# Sheet1.net
KiCad netlist of a schematic drawn in Altium Designer
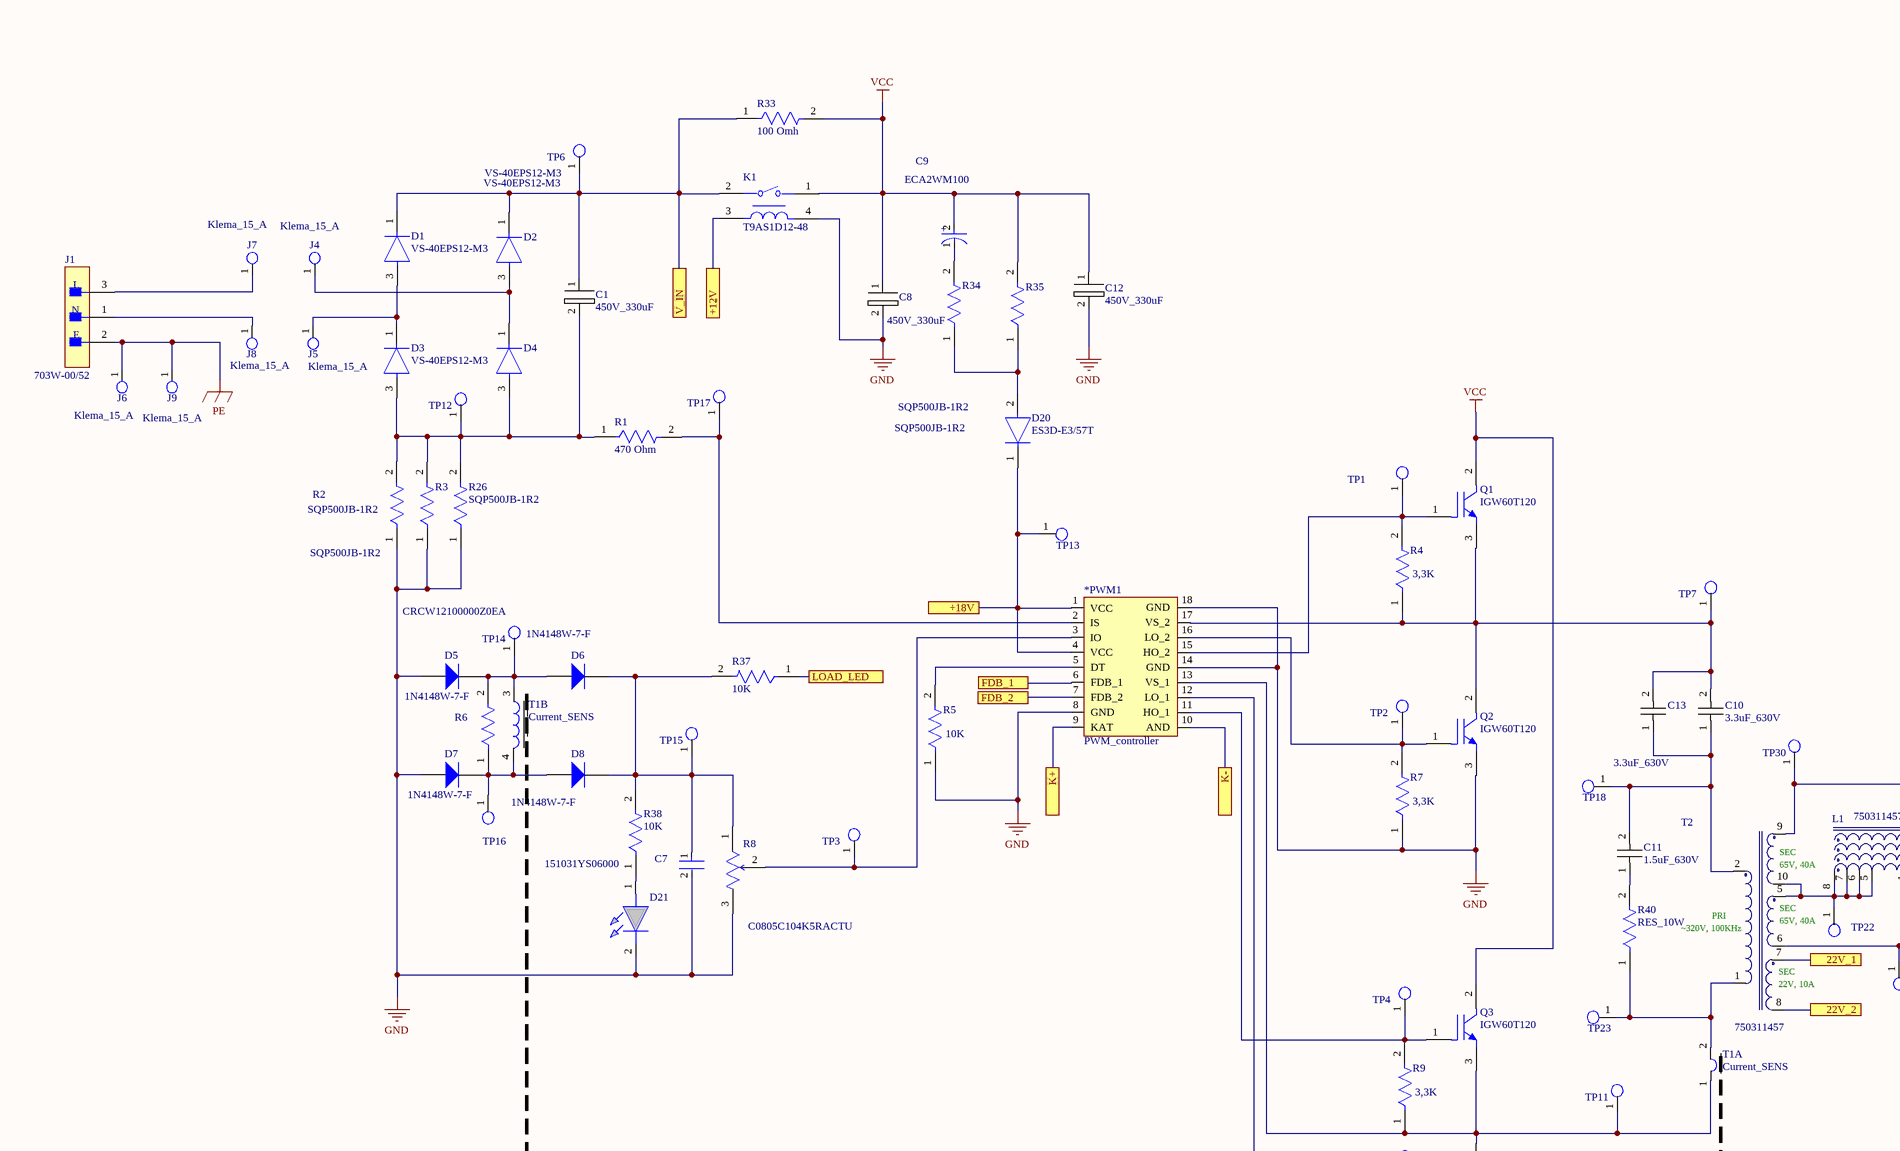
[diagram p0: Sheet1.SchDoc, top left]
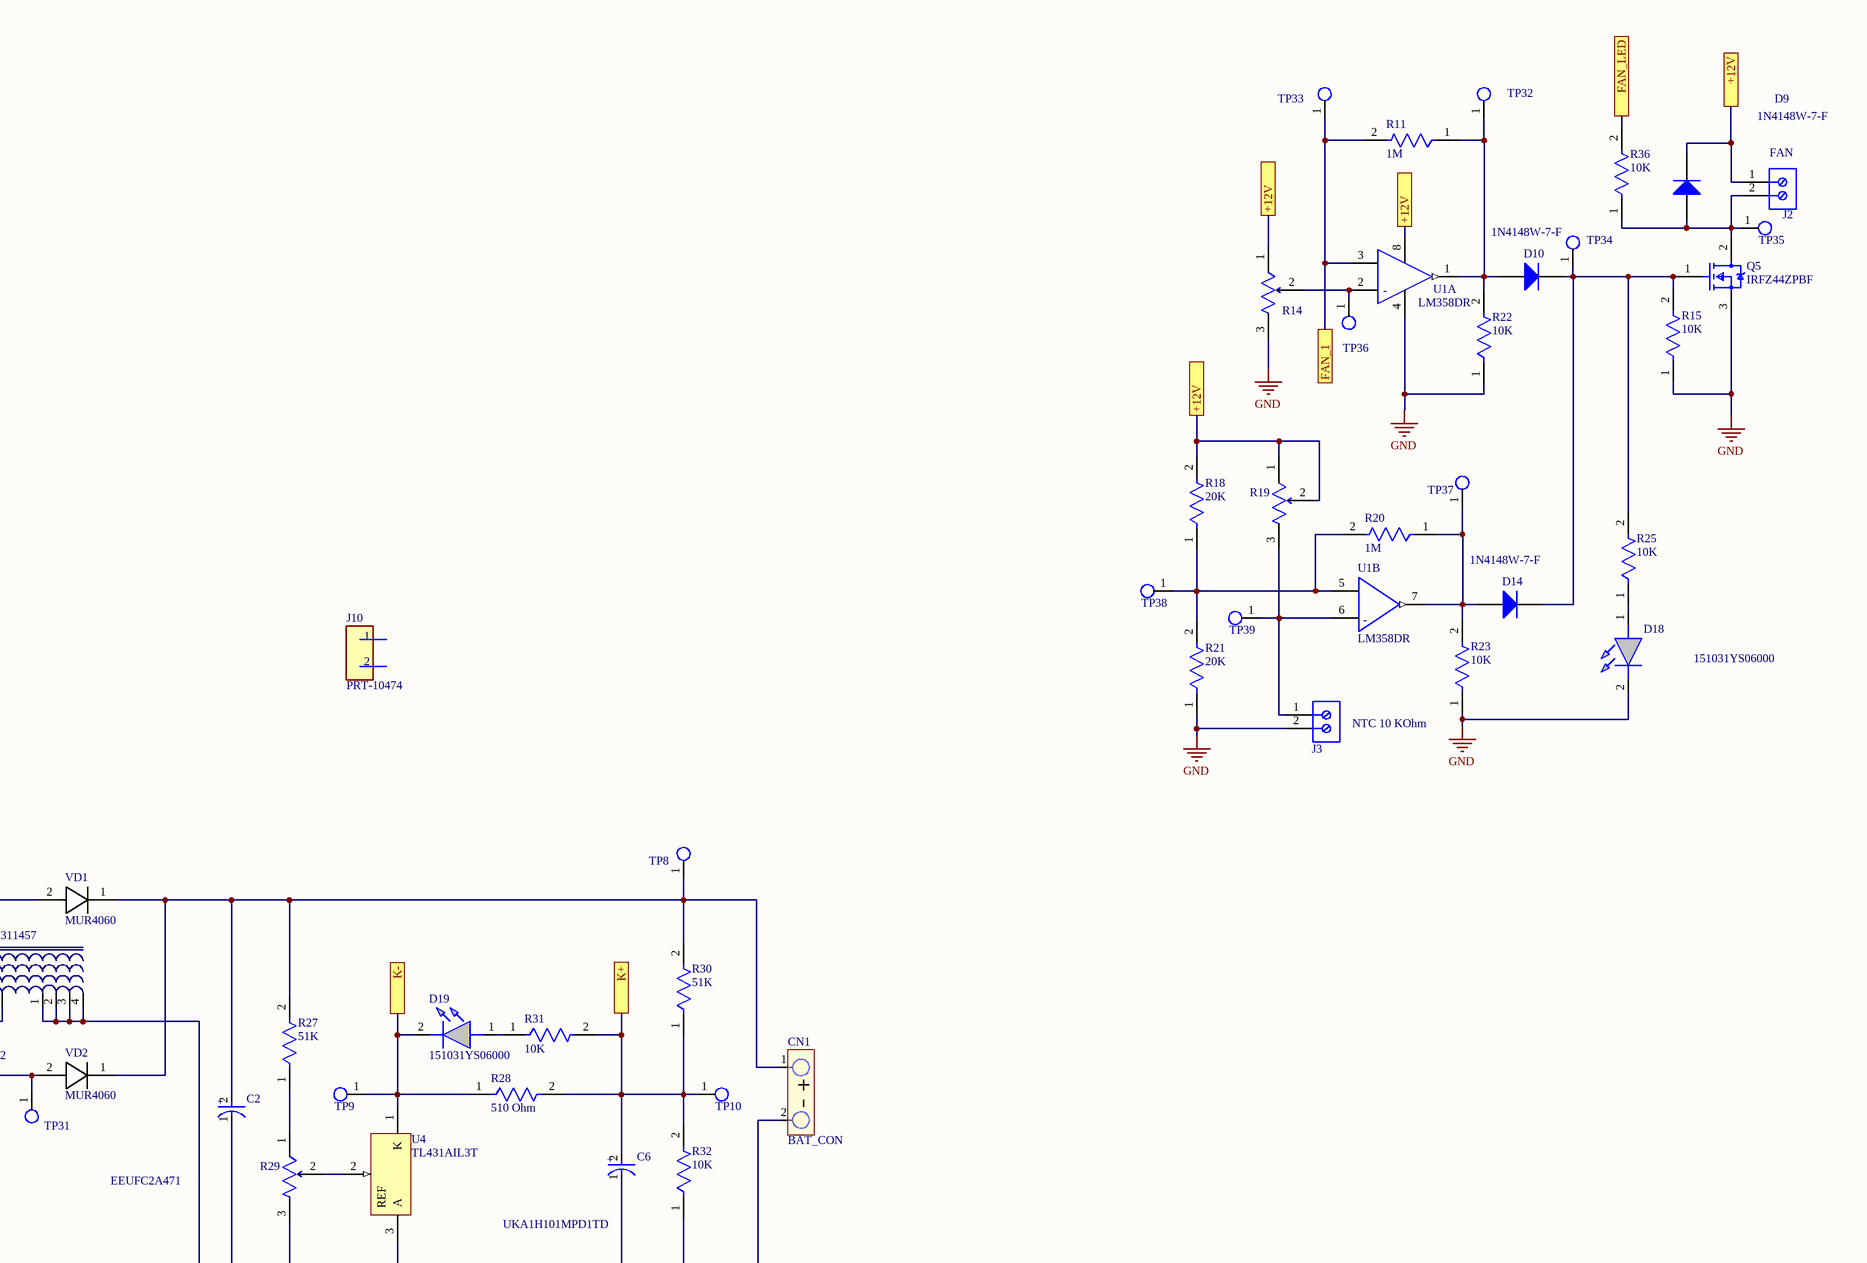
[diagram p1: Sheet1.SchDoc, top right]
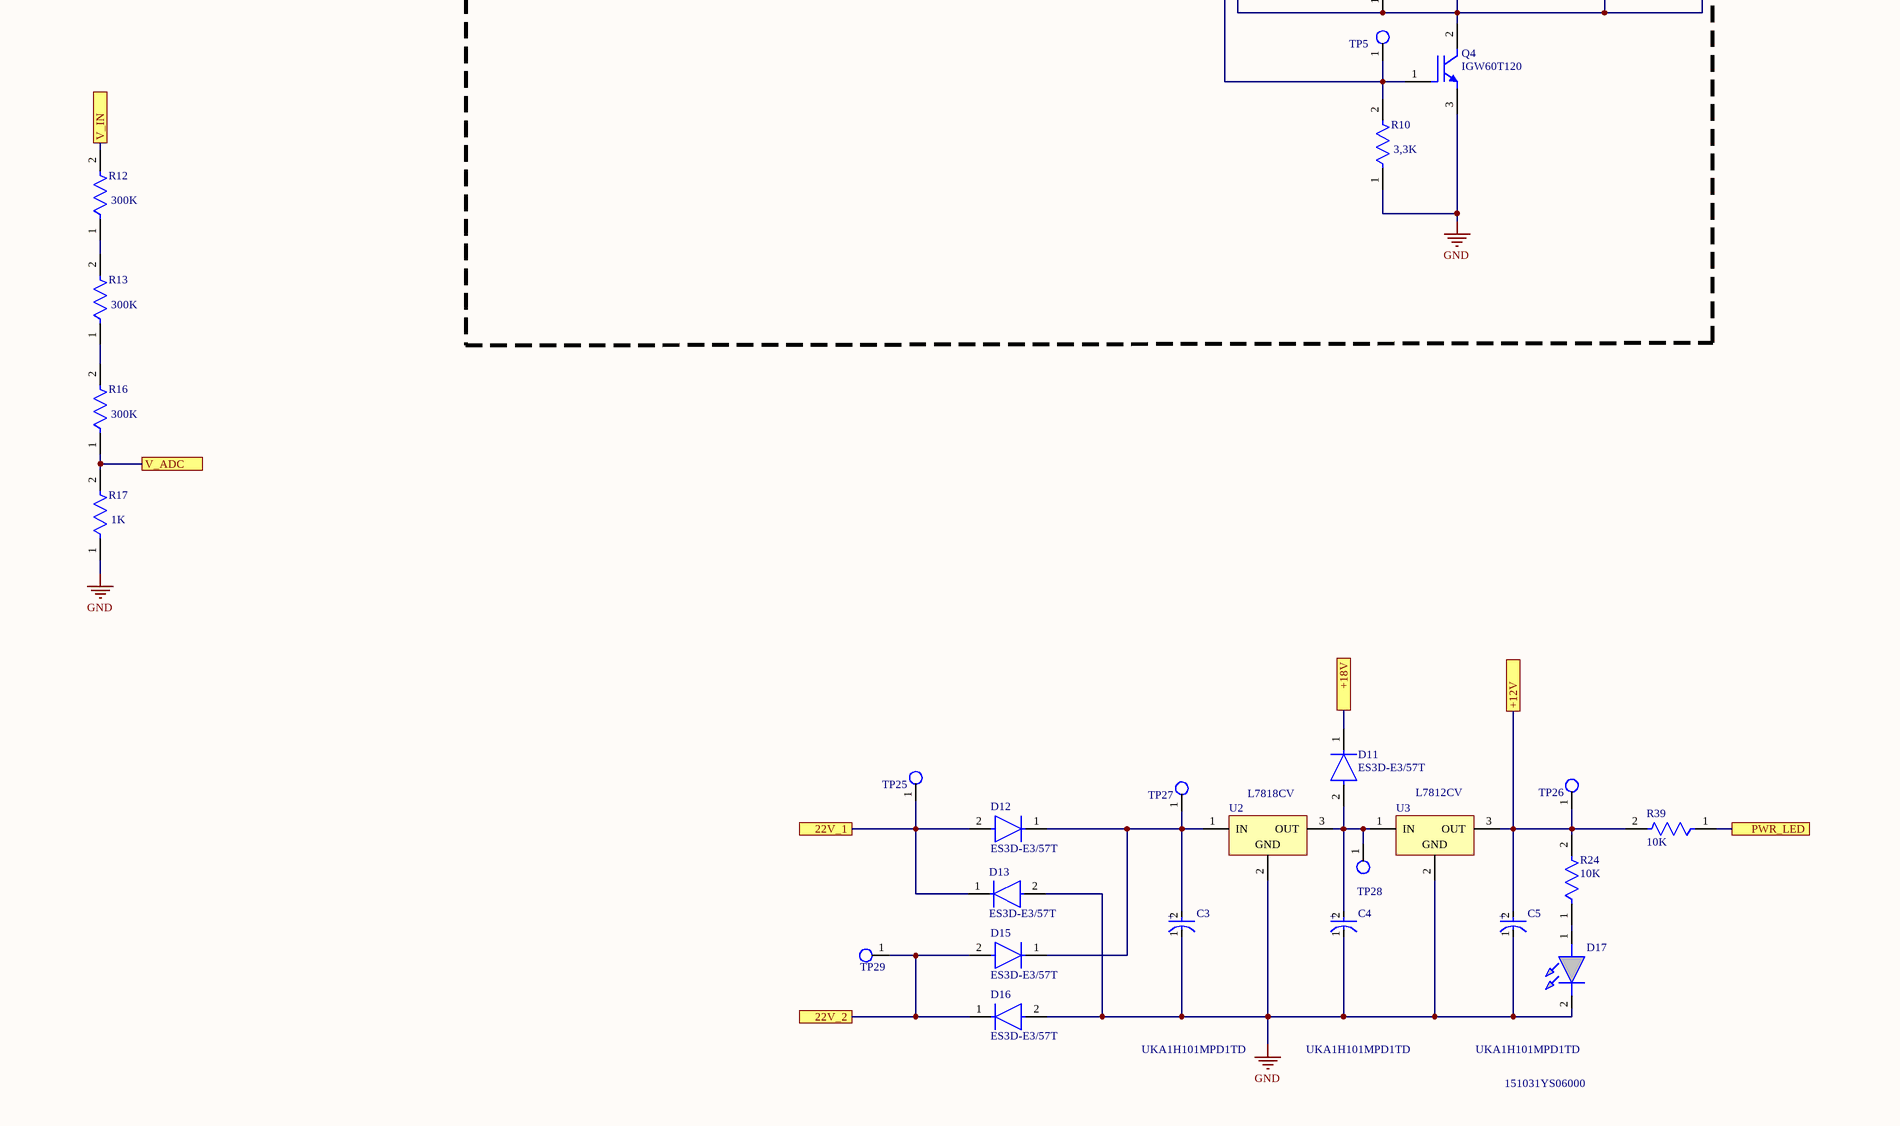
[diagram p2: Sheet1.SchDoc, bottom left]
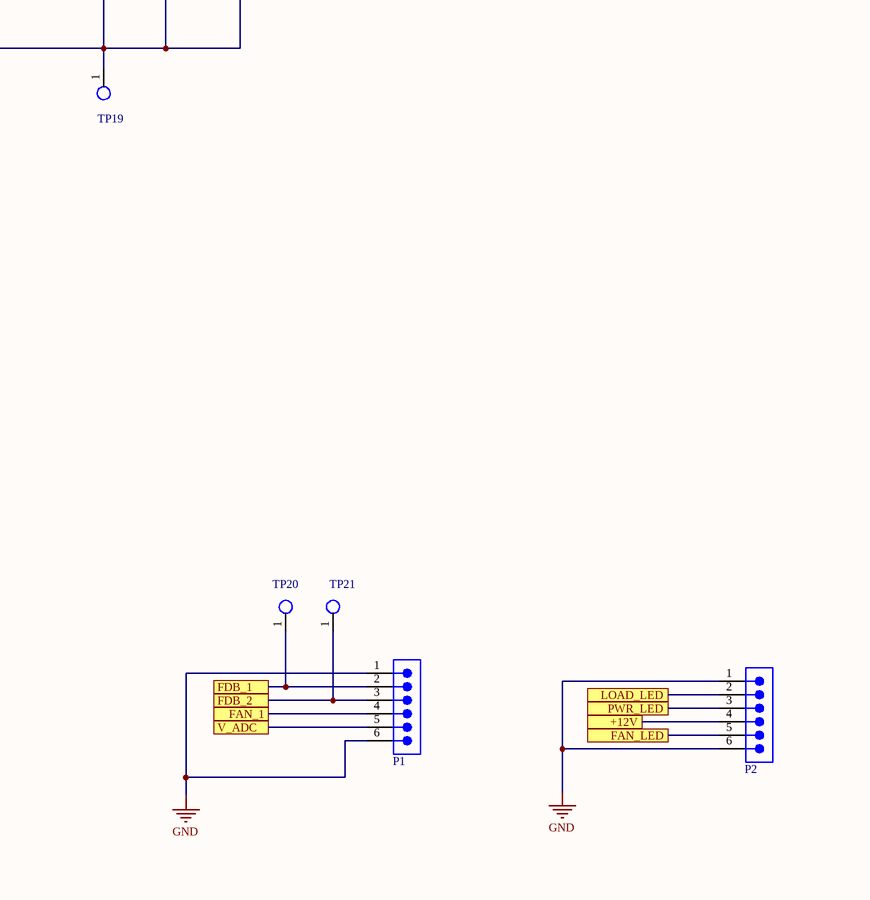
[diagram p3: Sheet1.SchDoc, bottom right]

(export (version "E")
  (design (tool "Eeschema 10.0.6"))
  (components
    (comp (ref "*PWM1")
      (value "PWM_controller")
      (footprint "PWM_controller")
      (libsource (lib "PWM_controller") (part "PWM_controller"))
    )
    (comp (ref "C1")
      (value "450V_330uF")
      (footprint "CAP_450V_330uF")
      (libsource (lib "CAP_450V_330uF") (part "CAP_450V_330uF"))
    )
    (comp (ref "C2")
      (value "EEUFC2A471")
      (footprint "FP-RAD-TH-D_16_0_5-L_40_2-MFG")
      (description "Aluminum Electrolytic Capacitors (Radial Lead Type) AEC-Q200 Qualified 470uF ±20% 100V")
      (fields (field (name "VOLTAGE") "100V") (field (name "TOLERANCE") "20%"))
      (libsource (lib "Altium Content Vault") (part "203bc49f2ac43e59fd269a8c329ed05"))
    )
    (comp (ref "C3")
      (value "UKA1H101MPD1TD")
      (footprint "FP-UKA1H101MPD1TD-MFG")
      (description "CAP ALUM 100UF 20% 50V RADIAL")
      (fields (field (name "TOLERANCE") "20%"))
      (libsource (lib "Altium Content Vault") (part "203bc49f2ac43e59fd269a8c329ed05"))
    )
    (comp (ref "C4")
      (value "UKA1H101MPD1TD")
      (footprint "FP-UKA1H101MPD1TD-MFG")
      (description "CAP ALUM 100UF 20% 50V RADIAL")
      (fields (field (name "TOLERANCE") "20%"))
      (libsource (lib "Altium Content Vault") (part "203bc49f2ac43e59fd269a8c329ed05"))
    )
    (comp (ref "C5")
      (value "UKA1H101MPD1TD")
      (footprint "FP-UKA1H101MPD1TD-MFG")
      (description "CAP ALUM 100UF 20% 50V RADIAL")
      (fields (field (name "TOLERANCE") "20%"))
      (libsource (lib "Altium Content Vault") (part "203bc49f2ac43e59fd269a8c329ed05"))
    )
    (comp (ref "C6")
      (value "UKA1H101MPD1TD")
      (footprint "FP-UKA1H101MPD1TD-MFG")
      (description "CAP ALUM 100UF 20% 50V RADIAL")
      (fields (field (name "TOLERANCE") "20%"))
      (libsource (lib "Altium Content Vault") (part "203bc49f2ac43e59fd269a8c329ed05"))
    )
    (comp (ref "C7")
      (value "C0805C104K5RACTU")
      (footprint "FP-C0805C-DN-MFG")
      (description "CAP CER 0.1UF 50V X7R 0805")
      (fields
        (field (name "MANUFACTURER") "KEMET")
        (field (name "OCTOPART") "https://octopart.com/c0805c104k5ractu-kemet-143926")
      )
      (libsource (lib "Altium Content Vault") (part "b4654b650e69147ec39a6b967a45e02"))
    )
    (comp (ref "C8")
      (value "450V_330uF")
      (footprint "CAP_450V_470uF")
      (libsource (lib "CAP_450V_330uF") (part "CAP_450V_330uF"))
    )
    (comp (ref "C9")
      (value "ECA2WM100")
      (footprint "FP-RAD-TH-D_12_5_0_5-L_20-MFG")
      (description "Aluminum Electrolytic Capacitors (Radial Lead Type) 10uF ±20% 450V")
      (fields (field (name "TOLERANCE") "20%") (field (name "VOLTAGE") "450V"))
      (libsource (lib "Altium Content Vault") (part "a00bbbee19879c290e62620ae7e47b1"))
    )
    (comp (ref "C10")
      (value "3.3uF_630V")
      (footprint "CAP_4.7uF_630V")
      (libsource (lib "CAP_3.3uF_630V") (part "3.3uF_630V"))
    )
    (comp (ref "C11")
      (value "1.5uF_630V")
      (footprint "CAP_1.5uf_400V")
      (libsource (lib "CAP_3.3uF_630V") (part "3.3uF_630V"))
    )
    (comp (ref "C12")
      (value "450V_330uF")
      (footprint "CAP_450V_470uF")
      (libsource (lib "CAP_450V_330uF") (part "CAP_450V_330uF"))
    )
    (comp (ref "C13")
      (value "3.3uF_630V")
      (footprint "CAP_4.7uF_630V")
      (libsource (lib "CAP_3.3uF_630V") (part "3.3uF_630V"))
    )
    (comp (ref "CN1")
      (value "BAT_CON")
      (footprint "Batarey_connector")
      (description "Batarey_connection")
      (libsource (lib "Batarey_connector") (part "BAT_CON"))
    )
    (comp (ref "D1")
      (value "VS-40EPS12-M3")
      (footprint "FP-96144-MFG")
      (description "DIODE GP 1.2KV 40A TO247AC")
      (libsource (lib "Altium Content Vault") (part "ac9d09a08f7f4319d7c77abc64a3d8a"))
    )
    (comp (ref "D2")
      (value "VS-40EPS12-M3")
      (footprint "FP-96144-MFG")
      (description "DIODE GP 1.2KV 40A TO247AC")
      (libsource (lib "Altium Content Vault") (part "ac9d09a08f7f4319d7c77abc64a3d8a"))
    )
    (comp (ref "D3")
      (value "VS-40EPS12-M3")
      (footprint "FP-96144-MFG")
      (description "DIODE GP 1.2KV 40A TO247AC")
      (libsource (lib "Altium Content Vault") (part "ac9d09a08f7f4319d7c77abc64a3d8a"))
    )
    (comp (ref "D4")
      (value "VS-40EPS12-M3")
      (footprint "FP-96144-MFG")
      (description "DIODE GP 1.2KV 40A TO247AC")
      (libsource (lib "Altium Content Vault") (part "ac9d09a08f7f4319d7c77abc64a3d8a"))
    )
    (comp (ref "D5")
      (value "1N4148W-7-F")
      (footprint "DIOD-SOD123-2_V")
      (description "Fast Switching Diode, 100 V, 0.15 A, -65 to 150 degC, 2-Pin?SOD123, RoHS, Tape and Reel")
      (fields (field (name "MANUFACTURER") "DiodesIncorporated"))
      (libsource (lib "Altium Content Vault") (part "D-AK-2"))
    )
    (comp (ref "D6")
      (value "1N4148W-7-F")
      (footprint "DIOD-SOD123-2_V")
      (description "Fast Switching Diode, 100 V, 0.15 A, -65 to 150 degC, 2-Pin?SOD123, RoHS, Tape and Reel")
      (fields (field (name "MANUFACTURER") "DiodesIncorporated"))
      (libsource (lib "Altium Content Vault") (part "D-AK-2"))
    )
    (comp (ref "D7")
      (value "1N4148W-7-F")
      (footprint "DIOD-SOD123-2_V")
      (description "Fast Switching Diode, 100 V, 0.15 A, -65 to 150 degC, 2-Pin?SOD123, RoHS, Tape and Reel")
      (fields (field (name "MANUFACTURER") "DiodesIncorporated"))
      (libsource (lib "Altium Content Vault") (part "D-AK-2"))
    )
    (comp (ref "D8")
      (value "1N4148W-7-F")
      (footprint "DIOD-SOD123-2_V")
      (description "Fast Switching Diode, 100 V, 0.15 A, -65 to 150 degC, 2-Pin?SOD123, RoHS, Tape and Reel")
      (fields (field (name "MANUFACTURER") "DiodesIncorporated"))
      (libsource (lib "Altium Content Vault") (part "D-AK-2"))
    )
    (comp (ref "D9")
      (value "1N4148W-7-F")
      (footprint "DIOD-SOD123-2_V")
      (description "Fast Switching Diode, 100 V, 0.15 A, -65 to 150 degC, 2-Pin?SOD123, RoHS, Tape and Reel")
      (fields (field (name "MANUFACTURER") "DiodesIncorporated"))
      (libsource (lib "Altium Content Vault") (part "D-AK-2"))
    )
    (comp (ref "D10")
      (value "1N4148W-7-F")
      (footprint "DIOD-SOD123-2_V")
      (description "Fast Switching Diode, 100 V, 0.15 A, -65 to 150 degC, 2-Pin?SOD123, RoHS, Tape and Reel")
      (fields (field (name "MANUFACTURER") "DiodesIncorporated"))
      (libsource (lib "Altium Content Vault") (part "D-AK-2"))
    )
    (comp (ref "D11")
      (value "ES3D-E3/57T")
      (footprint "FP-95402-MFG")
      (description "DIODE GEN PURP 200V 3A DO214AB")
      (fields
        (field (name "OCTOPART") "https://octopart.com/es3d-e3%2F57t-vishay-39550290")
        (field (name "MANUFACTURER") "Vishay")
      )
      (libsource (lib "Altium Content Vault") (part "d7152d700b627762746794eb795d46e"))
    )
    (comp (ref "D12")
      (value "ES3D-E3/57T")
      (footprint "FP-95402-MFG")
      (description "DIODE GEN PURP 200V 3A DO214AB")
      (fields
        (field (name "OCTOPART") "https://octopart.com/es3d-e3%2F57t-vishay-39550290")
        (field (name "MANUFACTURER") "Vishay")
      )
      (libsource (lib "Altium Content Vault") (part "d7152d700b627762746794eb795d46e"))
    )
    (comp (ref "D13")
      (value "ES3D-E3/57T")
      (footprint "FP-95402-MFG")
      (description "DIODE GEN PURP 200V 3A DO214AB")
      (fields
        (field (name "OCTOPART") "https://octopart.com/es3d-e3%2F57t-vishay-39550290")
        (field (name "MANUFACTURER") "Vishay")
      )
      (libsource (lib "Altium Content Vault") (part "d7152d700b627762746794eb795d46e"))
    )
    (comp (ref "D14")
      (value "1N4148W-7-F")
      (footprint "DIOD-SOD123-2_V")
      (description "Fast Switching Diode, 100 V, 0.15 A, -65 to 150 degC, 2-Pin?SOD123, RoHS, Tape and Reel")
      (fields (field (name "MANUFACTURER") "DiodesIncorporated"))
      (libsource (lib "Altium Content Vault") (part "D-AK-2"))
    )
    (comp (ref "D15")
      (value "ES3D-E3/57T")
      (footprint "FP-95402-MFG")
      (description "DIODE GEN PURP 200V 3A DO214AB")
      (fields
        (field (name "OCTOPART") "https://octopart.com/es3d-e3%2F57t-vishay-39550290")
        (field (name "MANUFACTURER") "Vishay")
      )
      (libsource (lib "Altium Content Vault") (part "d7152d700b627762746794eb795d46e"))
    )
    (comp (ref "D16")
      (value "ES3D-E3/57T")
      (footprint "FP-95402-MFG")
      (description "DIODE GEN PURP 200V 3A DO214AB")
      (fields
        (field (name "OCTOPART") "https://octopart.com/es3d-e3%2F57t-vishay-39550290")
        (field (name "MANUFACTURER") "Vishay")
      )
      (libsource (lib "Altium Content Vault") (part "d7152d700b627762746794eb795d46e"))
    )
    (comp (ref "D17")
      (value "151031YS06000")
      (footprint "LED_BLUE")
      (description "WURTH ELEKTRONIK - 151031YS06000 - LED, Yellow, Through Hole, T-1 (3mm), 30 mA, 2 V, 590 nm")
      (fields (field (name "MOUSER PART NUMBER") "710-151031YS06000"))
      (libsource (lib "Optic-LED") (part "151031YS06000"))
    )
    (comp (ref "D18")
      (value "151031YS06000")
      (footprint "Wurth_Electronics_0_MFG")
      (description "WURTH ELEKTRONIK - 151031YS06000 - LED, Yellow, Through Hole, T-1 (3mm), 30 mA, 2 V, 590 nm")
      (fields (field (name "MOUSER PART NUMBER") "710-151031YS06000"))
      (libsource (lib "Optic-LED") (part "151031YS06000"))
    )
    (comp (ref "D19")
      (value "151031YS06000")
      (footprint "LED_Yellow")
      (description "WURTH ELEKTRONIK - 151031YS06000 - LED, Yellow, Through Hole, T-1 (3mm), 30 mA, 2 V, 590 nm")
      (fields (field (name "MOUSER PART NUMBER") "710-151031YS06000"))
      (libsource (lib "Optic-LED") (part "151031YS06000"))
    )
    (comp (ref "D20")
      (value "ES3D-E3/57T")
      (footprint "FP-95402-MFG")
      (description "DIODE GEN PURP 200V 3A DO214AB")
      (fields
        (field (name "OCTOPART") "https://octopart.com/es3d-e3%2F57t-vishay-39550290")
        (field (name "MANUFACTURER") "Vishay")
      )
      (libsource (lib "Altium Content Vault") (part "d7152d700b627762746794eb795d46e"))
    )
    (comp (ref "D21")
      (value "151031YS06000")
      (footprint "LED_GREEN")
      (description "WURTH ELEKTRONIK - 151031YS06000 - LED, Yellow, Through Hole, T-1 (3mm), 30 mA, 2 V, 590 nm")
      (fields (field (name "MOUSER PART NUMBER") "710-151031YS06000"))
      (libsource (lib "Optic-LED") (part "151031YS06000"))
    )
    (comp (ref "J1")
      (value "703W-00/52")
      (footprint "FP-703W-00-52-MFG")
      (description "PWR ENT RCPT IEC320-C14 PNL SLDR")
      (libsource (lib "Altium Content Vault") (part "d3fa5aafac2488dd744475722bda3d4"))
    )
    (comp (ref "J2")
      (value "691137710002")
      (footprint "691137710002")
      (description "WR-TBL Series 1377 Horizontal Entry, THT, pitch 5mm, 2p")
      (fields (field (name "MANUFACTURER") "Wurth Elektronik"))
      (libsource (lib "Altium_WR-TBL (rev23a)") (part "691137710002"))
    )
    (comp (ref "J3")
      (value "691137710002")
      (footprint "691137710002")
      (description "WR-TBL Series 1377 Horizontal Entry, THT, pitch 5mm, 2p")
      (fields (field (name "MANUFACTURER") "Wurth Elektronik"))
      (libsource (lib "Altium_WR-TBL (rev23a)") (part "691137710002"))
    )
    (comp (ref "J4")
      (value "Klema_15_A")
      (footprint "Klema_PCB_15A")
      (libsource (lib "Klema PCB_15_A") (part "Klema_15_A"))
    )
    (comp (ref "J5")
      (value "Klema_15_A")
      (footprint "Klema_PCB_15A")
      (libsource (lib "Klema PCB_15_A") (part "Klema_15_A"))
    )
    (comp (ref "J6")
      (value "Klema_15_A")
      (footprint "Klema_PCB_15A")
      (libsource (lib "Klema PCB_15_A") (part "Klema_15_A"))
    )
    (comp (ref "J7")
      (value "Klema_15_A")
      (footprint "Klema_PCB_15A")
      (libsource (lib "Klema PCB_15_A") (part "Klema_15_A"))
    )
    (comp (ref "J8")
      (value "Klema_15_A")
      (footprint "Klema_PCB_15A")
      (libsource (lib "Klema PCB_15_A") (part "Klema_15_A"))
    )
    (comp (ref "J9")
      (value "Klema_15_A")
      (footprint "Klema_PCB_15A")
      (libsource (lib "Klema PCB_15_A") (part "Klema_15_A"))
    )
    (comp (ref "J10")
      (value "PRT-10474")
      (footprint "FP-PRT-10474-MFG")
      (description "XT60 CONNECTORS MALE/FEMALE PAIR")
      (libsource (lib "Altium Content Vault") (part "e9d95e9eb6564353a08a501d7ea6c79"))
    )
    (comp (ref "K1")
      (value "T9AS1D12-48")
      (footprint "NT90RNCS12CB")
      (description "RELAY GEN PURPOSE SPST 30A 48V")
      (libsource (lib "RelayNT90RNCS12CB") (part "CMP-03396-000117-1"))
    )
    (comp (ref "L1")
      (value "750311457")
      (footprint "Transformer")
      (description "Drosel")
      (fields (field (name "MANUFACTURER") "Wuerth Elektronik"))
      (libsource (lib "DROSEL") (part "DROSEL"))
    )
    (comp (ref "P1")
      (value "61900611121")
      (footprint "61900611121")
      (description "WR-WTB THT Male Vertical Locking Header, pitch 2.54mm, 6pins")
      (fields (field (name "MANUFACTURER") "Wurth Elektronik"))
      (libsource (lib "Altium_WR-WTB (rev22b)") (part "61900611121"))
    )
    (comp (ref "P2")
      (value "61900611121")
      (footprint "61900611121")
      (description "WR-WTB THT Male Vertical Locking Header, pitch 2.54mm, 6pins")
      (fields (field (name "MANUFACTURER") "Wurth Elektronik"))
      (libsource (lib "Altium_WR-WTB (rev22b)") (part "61900611121"))
    )
    (comp (ref "Q1")
      (value "IGW60T120")
      (footprint "TO-264-3")
      (description "Low Loss IGBT in TrenchStop and Fieldstop Technology, PG-TO247-3-44, Tube, Green")
      (fields (field (name "MANUFACTURER") "Infineon"))
      (libsource (lib "IGBT 60N120") (part "CMP-1168-00042-1"))
    )
    (comp (ref "Q2")
      (value "IGW60T120")
      (footprint "TO-264-3")
      (description "Low Loss IGBT in TrenchStop and Fieldstop Technology, PG-TO247-3-44, Tube, Green")
      (fields (field (name "MANUFACTURER") "Infineon"))
      (libsource (lib "IGBT 60N120") (part "CMP-1168-00042-1"))
    )
    (comp (ref "Q3")
      (value "IGW60T120")
      (footprint "TO-264-3")
      (description "Low Loss IGBT in TrenchStop and Fieldstop Technology, PG-TO247-3-44, Tube, Green")
      (fields (field (name "MANUFACTURER") "Infineon"))
      (libsource (lib "IGBT 60N120") (part "CMP-1168-00042-1"))
    )
    (comp (ref "Q4")
      (value "IGW60T120")
      (footprint "TO-264-3")
      (description "Low Loss IGBT in TrenchStop and Fieldstop Technology, PG-TO247-3-44, Tube, Green")
      (fields (field (name "MANUFACTURER") "Infineon"))
      (libsource (lib "IGBT 60N120") (part "CMP-1168-00042-1"))
    )
    (comp (ref "Q5")
      (value "IRFZ44ZPBF")
      (footprint "FP-PG-TO220-3-MFG")
      (description "MOSFET N-CH 55V 51A TO220AB")
      (libsource (lib "Altium Content Vault") (part "b09f7f152735e370c1ea22a33fa83d6"))
    )
    (comp (ref "R1")
      (value "470 Ohm")
      (footprint "FP-CRCW0805-e3-MFG")
      (description "RES Thick Film, 470Ω, 1%, 0.125W, 100ppm/°C, 0805")
      (fields (field (name "TOLERANCE") "1%"))
      (libsource (lib "Pasive_components") (part "CMP-2001-04908-2"))
    )
    (comp (ref "R2")
      (value "SQP500JB-1R2")
      (footprint "FP-SQP500-MFG")
      (description "RES 1.2 OHM 5W 5% AXIAL")
      (fields
        (field (name "OCTOPART") "https://octopart.com/sqp500jb-1r2-yageo-1162571")
        (field (name "MANUFACTURER") "Yageo")
      )
      (libsource (lib "Pasive_components") (part "CMP-03413-000003-1"))
    )
    (comp (ref "R3")
      (value "SQP500JB-1R2")
      (footprint "FP-SQP500-MFG")
      (description "RES 1.2 OHM 5W 5% AXIAL")
      (fields
        (field (name "OCTOPART") "https://octopart.com/sqp500jb-1r2-yageo-1162571")
        (field (name "MANUFACTURER") "Yageo")
      )
      (libsource (lib "Pasive_components") (part "CMP-03413-000003-1"))
    )
    (comp (ref "R4")
      (value "3,3K")
      (footprint "FP-CRCW1210-e3-IPC_A")
      (description "RES SMD 3,3K OHM 1% 1/2W 1992")
      (libsource (lib "Pasive_components") (part "CMP-2005-01987-2"))
    )
    (comp (ref "R5")
      (value "10K")
      (footprint "FP-CRCW1210-e3-IPC_A")
      (description "RES SMD 10K OHM 1% 1/2W 1992")
      (libsource (lib "Pasive_components") (part "CMP-2005-01987-2"))
    )
    (comp (ref "R6")
      (value "CRCW12100000Z0EA")
      (footprint "FP-CRCW1210-e3-IPC_A")
      (description "RES SMD 205K OHM 1% 1/2W 1992")
      (libsource (lib "Pasive_components") (part "CMP-2005-01987-2"))
    )
    (comp (ref "R7")
      (value "3,3K")
      (footprint "FP-CRCW1210-e3-IPC_A")
      (description "RES SMD 3,3K OHM 1% 1/2W 1992")
      (libsource (lib "Pasive_components") (part "CMP-2005-01987-2"))
    )
    (comp (ref "R8")
      (value "3296W-1-202LF")
      (footprint "Bourns_3296W_MFG")
      (libsource (lib "Pasive_components") (part "3296W-1-202LF"))
    )
    (comp (ref "R9")
      (value "3,3K")
      (footprint "FP-CRCW1210-e3-IPC_A")
      (description "RES SMD 3,3K OHM 1% 1/2W 1992")
      (libsource (lib "Pasive_components") (part "CMP-2005-01987-2"))
    )
    (comp (ref "R10")
      (value "3,3K")
      (footprint "FP-CRCW1210-e3-IPC_A")
      (description "RES SMD 3,3K OHM 1% 1/2W 1992")
      (libsource (lib "Pasive_components") (part "CMP-2005-01987-2"))
    )
    (comp (ref "R11")
      (value "1M")
      (footprint "FP-CRCW0805-e3-MFG")
      (description "RES Thick Film, 1MΩ, 1%, 0.125W, 100ppm/°C, 0805")
      (fields (field (name "TOLERANCE") "1%"))
      (libsource (lib "Pasive_components") (part "CMP-2001-04908-2"))
    )
    (comp (ref "R12")
      (value "300K")
      (footprint "FP-CRCW1210-e3-IPC_A")
      (description "RES SMD 300K OHM 1% 1/2W 1992")
      (libsource (lib "Pasive_components") (part "CMP-2005-01987-2"))
    )
    (comp (ref "R13")
      (value "300K")
      (footprint "FP-CRCW1210-e3-IPC_A")
      (description "RES SMD 300K OHM 1% 1/2W 1992")
      (libsource (lib "Pasive_components") (part "CMP-2005-01987-2"))
    )
    (comp (ref "R14")
      (value "3296W-1-202LF")
      (footprint "Bourns_3296W_MFG")
      (libsource (lib "Pasive_components") (part "3296W-1-202LF"))
    )
    (comp (ref "R15")
      (value "10K")
      (footprint "FP-CRCW0805-e3-MFG")
      (description "RES Thick Film, 10KΩ, 1%, 0.125W, 100ppm/°C, 0805")
      (fields (field (name "TOLERANCE") "1%"))
      (libsource (lib "Pasive_components") (part "CMP-2001-04908-2"))
    )
    (comp (ref "R16")
      (value "300K")
      (footprint "FP-CRCW1210-e3-IPC_A")
      (description "RES SMD 300K OHM 1% 1/2W 1992")
      (libsource (lib "Pasive_components") (part "CMP-2005-01987-2"))
    )
    (comp (ref "R17")
      (value "1K")
      (footprint "FP-CRCW1210-e3-IPC_A")
      (description "RES SMD 1K OHM 1% 1/2W 1992")
      (libsource (lib "Pasive_components") (part "CMP-2005-01987-2"))
    )
    (comp (ref "R18")
      (value "20K")
      (footprint "FP-CRCW0805-e3-MFG")
      (description "RES Thick Film, 20KΩ, 1%, 0.125W, 100ppm/°C, 0805")
      (fields (field (name "TOLERANCE") "1%"))
      (libsource (lib "Pasive_components") (part "CMP-2001-04908-2"))
    )
    (comp (ref "R19")
      (value "3296W-1-202LF")
      (footprint "Bourns_3296W_MFG")
      (libsource (lib "Pasive_components") (part "3296W-1-202LF"))
    )
    (comp (ref "R20")
      (value "1M")
      (footprint "FP-CRCW0805-e3-MFG")
      (description "RES Thick Film, 1MΩ, 1%, 0.125W, 100ppm/°C, 0805")
      (fields (field (name "TOLERANCE") "1%"))
      (libsource (lib "Pasive_components") (part "CMP-2001-04908-2"))
    )
    (comp (ref "R21")
      (value "20K")
      (footprint "FP-CRCW0805-e3-MFG")
      (description "RES Thick Film, 20KΩ, 1%, 0.125W, 100ppm/°C, 0805")
      (fields (field (name "TOLERANCE") "1%"))
      (libsource (lib "Pasive_components") (part "CMP-2001-04908-2"))
    )
    (comp (ref "R22")
      (value "10K")
      (footprint "FP-CRCW0805-e3-MFG")
      (description "RES Thick Film, 10KΩ, 1%, 0.125W, 100ppm/°C, 0805")
      (fields (field (name "TOLERANCE") "1%"))
      (libsource (lib "Pasive_components") (part "CMP-2001-04908-2"))
    )
    (comp (ref "R23")
      (value "10K")
      (footprint "FP-CRCW0805-e3-MFG")
      (description "RES Thick Film, 10KΩ, 1%, 0.125W, 100ppm/°C, 0805")
      (fields (field (name "TOLERANCE") "1%"))
      (libsource (lib "Pasive_components") (part "CMP-2001-04908-2"))
    )
    (comp (ref "R24")
      (value "10K")
      (footprint "FP-CRCW0805-e3-MFG")
      (description "RES Thick Film, 10KΩ, 1%, 0.125W, 100ppm/°C, 0805")
      (fields (field (name "TOLERANCE") "1%"))
      (libsource (lib "Pasive_components") (part "CMP-2001-04908-2"))
    )
    (comp (ref "R25")
      (value "10K")
      (footprint "FP-CRCW0805-e3-MFG")
      (description "RES Thick Film, 10KΩ, 1%, 0.125W, 100ppm/°C, 0805")
      (fields (field (name "TOLERANCE") "1%"))
      (libsource (lib "Pasive_components") (part "CMP-2001-04908-2"))
    )
    (comp (ref "R26")
      (value "SQP500JB-1R2")
      (footprint "FP-SQP500-MFG")
      (description "RES 1.2 OHM 5W 5% AXIAL")
      (fields
        (field (name "OCTOPART") "https://octopart.com/sqp500jb-1r2-yageo-1162571")
        (field (name "MANUFACTURER") "Yageo")
      )
      (libsource (lib "Pasive_components") (part "CMP-03413-000003-1"))
    )
    (comp (ref "R27")
      (value "51K")
      (footprint "FP-CRCW0805-e3-MFG")
      (description "RES Thick Film, 51KΩ, 1%, 0.125W, 100ppm/°C, 0805")
      (fields (field (name "TOLERANCE") "1%"))
      (libsource (lib "Pasive_components") (part "CMP-2001-04908-2"))
    )
    (comp (ref "R28")
      (value "510 Ohm")
      (footprint "FP-CRCW0805-e3-MFG")
      (description "RES Thick Film, 510Ω, 1%, 0.125W, 100ppm/°C, 0805")
      (fields (field (name "TOLERANCE") "1%"))
      (libsource (lib "Pasive_components") (part "CMP-2001-04908-2"))
    )
    (comp (ref "R29")
      (value "3296W-1-202LF")
      (footprint "Bourns_3296W_MFG")
      (libsource (lib "Pasive_components") (part "3296W-1-202LF"))
    )
    (comp (ref "R30")
      (value "51K")
      (footprint "FP-CRCW0805-e3-MFG")
      (description "RES Thick Film, 51KΩ, 1%, 0.125W, 100ppm/°C, 0805")
      (fields (field (name "TOLERANCE") "1%"))
      (libsource (lib "Pasive_components") (part "CMP-2001-04908-2"))
    )
    (comp (ref "R31")
      (value "10K")
      (footprint "FP-CRCW0805-e3-MFG")
      (description "RES Thick Film, 10KΩ, 1%, 0.125W, 100ppm/°C, 0805")
      (fields (field (name "TOLERANCE") "1%"))
      (libsource (lib "Pasive_components") (part "CMP-2001-04908-2"))
    )
    (comp (ref "R32")
      (value "10K")
      (footprint "FP-CRCW0805-e3-MFG")
      (description "RES Thick Film, 10KΩ, 1%, 0.125W, 100ppm/°C, 0805")
      (fields (field (name "TOLERANCE") "1%"))
      (libsource (lib "Pasive_components") (part "CMP-2001-04908-2"))
    )
    (comp (ref "R33") (value "100 Omh") (footprint "10W 3 Ohm") (libsource (lib "") (part "RES_10W_1")))
    (comp (ref "R34")
      (value "SQP500JB-1R2")
      (footprint "FP-SQP500-MFG")
      (description "RES 1.2 OHM 5W 5% AXIAL")
      (fields
        (field (name "OCTOPART") "https://octopart.com/sqp500jb-1r2-yageo-1162571")
        (field (name "MANUFACTURER") "Yageo")
      )
      (libsource (lib "Pasive_components") (part "CMP-03413-000003-1"))
    )
    (comp (ref "R35")
      (value "SQP500JB-1R2")
      (footprint "FP-SQP500-MFG")
      (description "RES 1.2 OHM 5W 5% AXIAL")
      (fields
        (field (name "OCTOPART") "https://octopart.com/sqp500jb-1r2-yageo-1162571")
        (field (name "MANUFACTURER") "Yageo")
      )
      (libsource (lib "Pasive_components") (part "CMP-03413-000003-1"))
    )
    (comp (ref "R36")
      (value "10K")
      (footprint "FP-CRCW0805-e3-MFG")
      (description "RES Thick Film, 10KΩ, 1%, 0.125W, 100ppm/°C, 0805")
      (fields (field (name "TOLERANCE") "1%"))
      (libsource (lib "Pasive_components") (part "CMP-2001-04908-2"))
    )
    (comp (ref "R37")
      (value "10K")
      (footprint "FP-CRCW0805-e3-MFG")
      (description "RES Thick Film, 10KΩ, 1%, 0.125W, 100ppm/°C, 0805")
      (fields (field (name "TOLERANCE") "1%"))
      (libsource (lib "Pasive_components") (part "CMP-2001-04908-2"))
    )
    (comp (ref "R38")
      (value "10K")
      (footprint "FP-CRCW0805-e3-MFG")
      (description "RES Thick Film, 10KΩ, 1%, 0.125W, 100ppm/°C, 0805")
      (fields (field (name "TOLERANCE") "1%"))
      (libsource (lib "Pasive_components") (part "CMP-2001-04908-2"))
    )
    (comp (ref "R39")
      (value "10K")
      (footprint "FP-CRCW0805-e3-MFG")
      (description "RES Thick Film, 10KΩ, 1%, 0.125W, 100ppm/°C, 0805")
      (fields (field (name "TOLERANCE") "1%"))
      (libsource (lib "Pasive_components") (part "CMP-2001-04908-2"))
    )
    (comp (ref "R40") (value "RES_10W") (footprint "10W 3 Ohm") (libsource (lib "RES_10W") (part "RES_10W")))
    (comp (ref "T1")
      (value "Current_SENS")
      (footprint "Current_SENS")
      (libsource (lib "") (part "Current_SENS_1"))
    )
    (comp (ref "T2")
      (value "750311457")
      (footprint "Transformer")
      (description "Transformer")
      (fields (field (name "MANUFACTURER") "Wuerth Elektronik"))
      (libsource (lib "Transformer_3") (part "Transformer"))
    )
    (comp (ref "TP1")
      (value "Test_Point_PCB")
      (footprint "Test_Point")
      (description "Test_Point")
      (libsource (lib "Test_Point") (part "TP_PCB?"))
    )
    (comp (ref "TP2")
      (value "Test_Point_PCB")
      (footprint "Test_Point")
      (description "Test_Point")
      (libsource (lib "Test_Point") (part "TP_PCB?"))
    )
    (comp (ref "TP3")
      (value "Test_Point_PCB")
      (footprint "Test_Point")
      (description "Test_Point")
      (libsource (lib "Test_Point") (part "TP_PCB?"))
    )
    (comp (ref "TP4")
      (value "Test_Point_PCB")
      (footprint "Test_Point")
      (description "Test_Point")
      (libsource (lib "Test_Point") (part "TP_PCB?"))
    )
    (comp (ref "TP5")
      (value "Test_Point_PCB")
      (footprint "Test_Point")
      (description "Test_Point")
      (libsource (lib "Test_Point") (part "TP_PCB?"))
    )
    (comp (ref "TP6")
      (value "Test_Point_PCB")
      (footprint "Test_Point")
      (description "Test_Point")
      (libsource (lib "Test_Point") (part "TP_PCB?"))
    )
    (comp (ref "TP7")
      (value "Test_Point_PCB")
      (footprint "Test_Point")
      (description "Test_Point")
      (libsource (lib "Test_Point") (part "TP_PCB?"))
    )
    (comp (ref "TP8")
      (value "Test_Point_PCB")
      (footprint "Test_Point")
      (description "Test_Point")
      (libsource (lib "Test_Point") (part "TP_PCB?"))
    )
    (comp (ref "TP9")
      (value "Test_Point_PCB")
      (footprint "Test_Point")
      (description "Test_Point")
      (libsource (lib "Test_Point") (part "TP_PCB?"))
    )
    (comp (ref "TP10")
      (value "Test_Point_PCB")
      (footprint "Test_Point")
      (description "Test_Point")
      (libsource (lib "Test_Point") (part "TP_PCB?"))
    )
    (comp (ref "TP11")
      (value "Test_Point_PCB")
      (footprint "Test_Point")
      (description "Test_Point")
      (libsource (lib "Test_Point") (part "TP_PCB?"))
    )
    (comp (ref "TP12")
      (value "Test_Point_PCB")
      (footprint "Test_Point")
      (description "Test_Point")
      (libsource (lib "Test_Point") (part "TP_PCB?"))
    )
    (comp (ref "TP13")
      (value "Test_Point_PCB")
      (footprint "Test_Point")
      (description "Test_Point")
      (libsource (lib "Test_Point") (part "TP_PCB?"))
    )
    (comp (ref "TP14")
      (value "Test_Point_PCB")
      (footprint "Test_Point")
      (description "Test_Point")
      (libsource (lib "Test_Point") (part "TP_PCB?"))
    )
    (comp (ref "TP15")
      (value "Test_Point_PCB")
      (footprint "Test_Point")
      (description "Test_Point")
      (libsource (lib "Test_Point") (part "TP_PCB?"))
    )
    (comp (ref "TP16")
      (value "Test_Point_PCB")
      (footprint "Test_Point")
      (description "Test_Point")
      (libsource (lib "Test_Point") (part "TP_PCB?"))
    )
    (comp (ref "TP17")
      (value "Test_Point_PCB")
      (footprint "Test_Point")
      (description "Test_Point")
      (libsource (lib "Test_Point") (part "TP_PCB?"))
    )
    (comp (ref "TP18")
      (value "Test_Point_PCB")
      (footprint "Test_Point")
      (description "Test_Point")
      (libsource (lib "Test_Point") (part "TP_PCB?"))
    )
    (comp (ref "TP19")
      (value "Test_Point_PCB")
      (footprint "Test_Point")
      (description "Test_Point")
      (libsource (lib "Test_Point") (part "TP_PCB?"))
    )
    (comp (ref "TP20")
      (value "Test_Point_PCB")
      (footprint "Test_Point")
      (description "Test_Point")
      (libsource (lib "Test_Point") (part "TP_PCB?"))
    )
    (comp (ref "TP21")
      (value "Test_Point_PCB")
      (footprint "Test_Point")
      (description "Test_Point")
      (libsource (lib "Test_Point") (part "TP_PCB?"))
    )
    (comp (ref "TP22")
      (value "Test_Point_PCB")
      (footprint "Test_Point")
      (description "Test_Point")
      (libsource (lib "Test_Point") (part "TP_PCB?"))
    )
    (comp (ref "TP23")
      (value "Test_Point_PCB")
      (footprint "Test_Point")
      (description "Test_Point")
      (libsource (lib "Test_Point") (part "TP_PCB?"))
    )
    (comp (ref "TP25")
      (value "Test_Point_PCB")
      (footprint "Test_Point")
      (description "Test_Point")
      (libsource (lib "Test_Point") (part "TP_PCB?"))
    )
    (comp (ref "TP26")
      (value "Test_Point_PCB")
      (footprint "Test_Point")
      (description "Test_Point")
      (libsource (lib "Test_Point") (part "TP_PCB?"))
    )
    (comp (ref "TP27")
      (value "Test_Point_PCB")
      (footprint "Test_Point")
      (description "Test_Point")
      (libsource (lib "Test_Point") (part "TP_PCB?"))
    )
    (comp (ref "TP28")
      (value "Test_Point_PCB")
      (footprint "Test_Point")
      (description "Test_Point")
      (libsource (lib "Test_Point") (part "TP_PCB?"))
    )
    (comp (ref "TP29")
      (value "Test_Point_PCB")
      (footprint "Test_Point")
      (description "Test_Point")
      (libsource (lib "Test_Point") (part "TP_PCB?"))
    )
    (comp (ref "TP30")
      (value "Test_Point_PCB")
      (footprint "Test_Point")
      (description "Test_Point")
      (libsource (lib "Test_Point") (part "TP_PCB?"))
    )
    (comp (ref "TP31")
      (value "Test_Point_PCB")
      (footprint "Test_Point")
      (description "Test_Point")
      (libsource (lib "Test_Point") (part "TP_PCB?"))
    )
    (comp (ref "TP32")
      (value "Test_Point_PCB")
      (footprint "Test_Point")
      (description "Test_Point")
      (libsource (lib "Test_Point") (part "TP_PCB?"))
    )
    (comp (ref "TP33")
      (value "Test_Point_PCB")
      (footprint "Test_Point")
      (description "Test_Point")
      (libsource (lib "Test_Point") (part "TP_PCB?"))
    )
    (comp (ref "TP34")
      (value "Test_Point_PCB")
      (footprint "Test_Point")
      (description "Test_Point")
      (libsource (lib "Test_Point") (part "TP_PCB?"))
    )
    (comp (ref "TP35")
      (value "Test_Point_PCB")
      (footprint "Test_Point")
      (description "Test_Point")
      (libsource (lib "Test_Point") (part "TP_PCB?"))
    )
    (comp (ref "TP36")
      (value "Test_Point_PCB")
      (footprint "Test_Point")
      (description "Test_Point")
      (libsource (lib "Test_Point") (part "TP_PCB?"))
    )
    (comp (ref "TP37")
      (value "Test_Point_PCB")
      (footprint "Test_Point")
      (description "Test_Point")
      (libsource (lib "Test_Point") (part "TP_PCB?"))
    )
    (comp (ref "TP38")
      (value "Test_Point_PCB")
      (footprint "Test_Point")
      (description "Test_Point")
      (libsource (lib "Test_Point") (part "TP_PCB?"))
    )
    (comp (ref "TP39")
      (value "Test_Point_PCB")
      (footprint "Test_Point")
      (description "Test_Point")
      (libsource (lib "Test_Point") (part "TP_PCB?"))
    )
    (comp (ref "U1")
      (value "LM358DR")
      (footprint "FP-D0008A-MFG")
      (description "IC OPAMP GP 2 CIRCUIT 8SOIC")
      (libsource (lib "Altium Content Vault") (part "0afdfe5f461d2cdd85604ff8654be97"))
    )
    (comp (ref "U2")
      (value "L7818CV")
      (footprint "TO220")
      (description "Positive Voltage Regulator, 18V, 3-Pin TO-220")
      (libsource (lib "Altium Content Vault") (part "PM-REG-L4940-SIL3"))
    )
    (comp (ref "U3")
      (value "L7812CV")
      (footprint "TO220")
      (description "Positive Voltage Regulator, 12V, 3-Pin TO-220")
      (libsource (lib "Altium Content Vault") (part "PM-REG-L4940-SIL3"))
    )
    (comp (ref "U4")
      (value "TL431AIL3T")
      (footprint "SOT23-3_L")
      (description "Programmable Voltage Reference, 2.5 to 36V, 3-Pin SOT23-3, Tape and Reel")
      (libsource (lib "Altium Content Vault") (part "PM-REF-431-IL3"))
    )
    (comp (ref "VD1") (value "MUR4060") (footprint "TO-247-2") (libsource (lib "MUR4060") (part "MUR4060")))
    (comp (ref "VD2") (value "MUR4060") (footprint "TO-247-2") (libsource (lib "MUR4060") (part "MUR4060")))
  )
  (nets
    (net (code "1") (name "/+12V") (class "Default")
      (node (ref "C5") (pin "2") (pinfunction "A_2") (pintype "passive"))
      (node (ref "D9") (pin "2") (pinfunction "K_2") (pintype "passive"))
      (node (ref "J2") (pin "1") (pinfunction "1_1") (pintype "passive"))
      (node (ref "K1") (pin "3") (pinfunction "3_3") (pintype "passive"))
      (node (ref "P2") (pin "4") (pinfunction "4_4") (pintype "passive"))
      (node (ref "R14") (pin "1") (pinfunction "CCW_1") (pintype "passive"))
      (node (ref "R18") (pin "2") (pinfunction "2_2") (pintype "passive"))
      (node (ref "R19") (pin "1") (pinfunction "CCW_1") (pintype "passive"))
      (node (ref "R19") (pin "2") (pinfunction "WIPER_2") (pintype "passive"))
      (node (ref "R24") (pin "2") (pinfunction "2_2") (pintype "passive"))
      (node (ref "R39") (pin "2") (pinfunction "2_2") (pintype "passive"))
      (node (ref "TP26") (pin "1") (pinfunction "G9_1") (pintype "passive"))
      (node (ref "U1") (pin "8") (pinfunction "V+_8") (pintype "power_in"))
      (node (ref "U3") (pin "3") (pinfunction "OUT_3") (pintype "power_in"))
    )
    (net (code "2") (name "/+18V") (class "Default")
      (node (ref "*PWM1") (pin "1") (pinfunction "VCC_1") (pintype "passive"))
      (node (ref "*PWM1") (pin "4") (pinfunction "VCC_4") (pintype "passive"))
      (node (ref "D11") (pin "1") (pinfunction "C_1") (pintype "passive"))
      (node (ref "D20") (pin "1") (pinfunction "C_1") (pintype "passive"))
      (node (ref "TP13") (pin "1") (pinfunction "G9_1") (pintype "passive"))
    )
    (net (code "3") (name "/22V_1") (class "Default")
      (node (ref "D12") (pin "2") (pinfunction "A_2") (pintype "passive"))
      (node (ref "D13") (pin "1") (pinfunction "C_1") (pintype "passive"))
      (node (ref "T2") (pin "7") (pinfunction "7_7") (pintype "passive"))
      (node (ref "TP25") (pin "1") (pinfunction "G9_1") (pintype "passive"))
    )
    (net (code "4") (name "/22V_2") (class "Default")
      (node (ref "D15") (pin "2") (pinfunction "A_2") (pintype "passive"))
      (node (ref "D16") (pin "1") (pinfunction "C_1") (pintype "passive"))
      (node (ref "T2") (pin "8") (pinfunction "8_8") (pintype "passive"))
      (node (ref "TP29") (pin "1") (pinfunction "G9_1") (pintype "passive"))
    )
    (net (code "5") (name "/FAN_1") (class "Default")
      (node (ref "P1") (pin "4") (pinfunction "4_4") (pintype "passive"))
      (node (ref "R11") (pin "2") (pinfunction "2_2") (pintype "passive"))
      (node (ref "TP33") (pin "1") (pinfunction "G9_1") (pintype "passive"))
      (node (ref "U1") (pin "3") (pinfunction "IN1+_3") (pintype "tri_state"))
    )
    (net (code "6") (name "/FAN_LED") (class "Default")
      (node (ref "P2") (pin "5") (pinfunction "5_5") (pintype "passive"))
      (node (ref "R36") (pin "2") (pinfunction "2_2") (pintype "passive"))
    )
    (net (code "7") (name "/FDB_1") (class "Default")
      (node (ref "*PWM1") (pin "6") (pinfunction "FDB_1_6") (pintype "passive"))
      (node (ref "P1") (pin "2") (pinfunction "2_2") (pintype "passive"))
      (node (ref "TP20") (pin "1") (pinfunction "G9_1") (pintype "passive"))
    )
    (net (code "8") (name "/FDB_2") (class "Default")
      (node (ref "*PWM1") (pin "7") (pinfunction "FDB_2_7") (pintype "passive"))
      (node (ref "P1") (pin "3") (pinfunction "3_3") (pintype "passive"))
      (node (ref "TP21") (pin "1") (pinfunction "G9_1") (pintype "passive"))
    )
    (net (code "9") (name "/K+") (class "Default")
      (node (ref "*PWM1") (pin "9") (pinfunction "KAT_9") (pintype "passive"))
      (node (ref "C6") (pin "2") (pinfunction "A_2") (pintype "passive"))
      (node (ref "R28") (pin "2") (pinfunction "2_2") (pintype "passive"))
      (node (ref "R30") (pin "1") (pinfunction "1_1") (pintype "passive"))
      (node (ref "R31") (pin "2") (pinfunction "2_2") (pintype "passive"))
      (node (ref "R32") (pin "2") (pinfunction "2_2") (pintype "passive"))
      (node (ref "TP10") (pin "1") (pinfunction "G9_1") (pintype "passive"))
    )
    (net (code "10") (name "/K-") (class "Default")
      (node (ref "*PWM1") (pin "10") (pinfunction "AND_10") (pintype "passive"))
      (node (ref "D19") (pin "2") (pinfunction "K_2") (pintype "passive"))
      (node (ref "R28") (pin "1") (pinfunction "1_1") (pintype "passive"))
      (node (ref "TP9") (pin "1") (pinfunction "G9_1") (pintype "passive"))
      (node (ref "U4") (pin "1") (pinfunction "K_1") (pintype "passive"))
    )
    (net (code "11") (name "/LOAD_LED") (class "Default")
      (node (ref "P2") (pin "2") (pinfunction "2_2") (pintype "passive"))
      (node (ref "R37") (pin "1") (pinfunction "1_1") (pintype "passive"))
    )
    (net (code "12") (name "/PWR_LED") (class "Default")
      (node (ref "P2") (pin "3") (pinfunction "3_3") (pintype "passive"))
      (node (ref "R39") (pin "1") (pinfunction "1_1") (pintype "passive"))
    )
    (net (code "13") (name "/V_ADC") (class "Default")
      (node (ref "P1") (pin "5") (pinfunction "5_5") (pintype "passive"))
      (node (ref "R16") (pin "1") (pinfunction "1_1") (pintype "passive"))
      (node (ref "R17") (pin "2") (pinfunction "2_2") (pintype "passive"))
    )
    (net (code "14") (name "/V_IN") (class "Default")
      (node (ref "C1") (pin "1") (pinfunction "1_1") (pintype "passive"))
      (node (ref "D1") (pin "1") (pinfunction "C_1") (pintype "passive"))
      (node (ref "D2") (pin "1") (pinfunction "C_1") (pintype "passive"))
      (node (ref "K1") (pin "2") (pinfunction "2_2") (pintype "passive"))
      (node (ref "R12") (pin "2") (pinfunction "2_2") (pintype "passive"))
      (node (ref "R33") (pin "1") (pinfunction "1_1") (pintype "passive"))
      (node (ref "TP6") (pin "1") (pinfunction "G9_1") (pintype "passive"))
    )
    (net (code "15") (name "GND") (class "Default")
      (node (ref "*PWM1") (pin "14") (pinfunction "GND_14") (pintype "passive"))
      (node (ref "*PWM1") (pin "18") (pinfunction "GND_18") (pintype "passive"))
      (node (ref "*PWM1") (pin "8") (pinfunction "GND_8") (pintype "passive"))
      (node (ref "C12") (pin "2") (pinfunction "2_2") (pintype "passive"))
      (node (ref "C3") (pin "1") (pinfunction "C_1") (pintype "passive"))
      (node (ref "C4") (pin "1") (pinfunction "C_1") (pintype "passive"))
      (node (ref "C5") (pin "1") (pinfunction "C_1") (pintype "passive"))
      (node (ref "C7") (pin "2") (pinfunction "2_2") (pintype "passive"))
      (node (ref "C8") (pin "2") (pinfunction "2_2") (pintype "passive"))
      (node (ref "D13") (pin "2") (pinfunction "A_2") (pintype "passive"))
      (node (ref "D16") (pin "2") (pinfunction "A_2") (pintype "passive"))
      (node (ref "D17") (pin "2") (pinfunction "K_2") (pintype "passive"))
      (node (ref "D18") (pin "2") (pinfunction "K_2") (pintype "passive"))
      (node (ref "D21") (pin "2") (pinfunction "K_2") (pintype "passive"))
      (node (ref "D5") (pin "1") (pinfunction "A_1") (pintype "passive"))
      (node (ref "D7") (pin "1") (pinfunction "A_1") (pintype "passive"))
      (node (ref "J3") (pin "2") (pinfunction "2_2") (pintype "passive"))
      (node (ref "K1") (pin "4") (pinfunction "4_4") (pintype "passive"))
      (node (ref "P1") (pin "1") (pinfunction "1_1") (pintype "passive"))
      (node (ref "P1") (pin "6") (pinfunction "6_6") (pintype "passive"))
      (node (ref "P2") (pin "1") (pinfunction "1_1") (pintype "passive"))
      (node (ref "P2") (pin "6") (pinfunction "6_6") (pintype "passive"))
      (node (ref "Q2") (pin "3") (pinfunction "E_3") (pintype "passive"))
      (node (ref "Q4") (pin "3") (pinfunction "E_3") (pintype "passive"))
      (node (ref "Q5") (pin "3") (pinfunction "S_3") (pintype "passive"))
      (node (ref "R10") (pin "1") (pinfunction "1_1") (pintype "passive"))
      (node (ref "R14") (pin "3") (pinfunction "CW_3") (pintype "passive"))
      (node (ref "R15") (pin "1") (pinfunction "1_1") (pintype "passive"))
      (node (ref "R17") (pin "1") (pinfunction "1_1") (pintype "passive"))
      (node (ref "R2") (pin "1") (pinfunction "1_1") (pintype "passive"))
      (node (ref "R21") (pin "1") (pinfunction "1_1") (pintype "passive"))
      (node (ref "R22") (pin "1") (pinfunction "1_1") (pintype "passive"))
      (node (ref "R23") (pin "1") (pinfunction "1_1") (pintype "passive"))
      (node (ref "R26") (pin "1") (pinfunction "1_1") (pintype "passive"))
      (node (ref "R3") (pin "1") (pinfunction "1_1") (pintype "passive"))
      (node (ref "R5") (pin "1") (pinfunction "1_1") (pintype "passive"))
      (node (ref "R7") (pin "1") (pinfunction "1_1") (pintype "passive"))
      (node (ref "R8") (pin "3") (pinfunction "CW_3") (pintype "passive"))
      (node (ref "U1") (pin "4") (pinfunction "V-_4") (pintype "power_in"))
      (node (ref "U2") (pin "2") (pinfunction "GND_2") (pintype "power_in"))
      (node (ref "U3") (pin "2") (pinfunction "GND_2") (pintype "power_in"))
    )
    (net (code "16") (name "Net-(*PWM1-DT)") (class "Default")
      (node (ref "*PWM1") (pin "5") (pinfunction "DT_5") (pintype "passive"))
      (node (ref "R5") (pin "2") (pinfunction "2_2") (pintype "passive"))
    )
    (net (code "17") (name "Net-(*PWM1-HO_1)") (class "Default")
      (node (ref "*PWM1") (pin "11") (pinfunction "HO_1_11") (pintype "passive"))
      (node (ref "Q3") (pin "1") (pinfunction "G_1") (pintype "passive"))
      (node (ref "R9") (pin "2") (pinfunction "2_2") (pintype "passive"))
      (node (ref "TP4") (pin "1") (pinfunction "G9_1") (pintype "passive"))
    )
    (net (code "18") (name "Net-(*PWM1-HO_2)") (class "Default")
      (node (ref "*PWM1") (pin "15") (pinfunction "HO_2_15") (pintype "passive"))
      (node (ref "Q1") (pin "1") (pinfunction "G_1") (pintype "passive"))
      (node (ref "R4") (pin "2") (pinfunction "2_2") (pintype "passive"))
      (node (ref "TP1") (pin "1") (pinfunction "G9_1") (pintype "passive"))
    )
    (net (code "19") (name "Net-(*PWM1-IO)") (class "Default")
      (node (ref "*PWM1") (pin "3") (pinfunction "IO_3") (pintype "passive"))
      (node (ref "R8") (pin "2") (pinfunction "WIPER_2") (pintype "passive"))
      (node (ref "TP3") (pin "1") (pinfunction "G9_1") (pintype "passive"))
    )
    (net (code "20") (name "Net-(*PWM1-IS)") (class "Default")
      (node (ref "*PWM1") (pin "2") (pinfunction "IS_2") (pintype "passive"))
      (node (ref "R1") (pin "2") (pinfunction "2_2") (pintype "passive"))
      (node (ref "TP17") (pin "1") (pinfunction "G9_1") (pintype "passive"))
    )
    (net (code "21") (name "Net-(*PWM1-LO_1)") (class "Default")
      (node (ref "*PWM1") (pin "12") (pinfunction "LO_1_12") (pintype "passive"))
      (node (ref "Q4") (pin "1") (pinfunction "G_1") (pintype "passive"))
      (node (ref "R10") (pin "2") (pinfunction "2_2") (pintype "passive"))
      (node (ref "TP5") (pin "1") (pinfunction "G9_1") (pintype "passive"))
    )
    (net (code "22") (name "Net-(*PWM1-LO_2)") (class "Default")
      (node (ref "*PWM1") (pin "16") (pinfunction "LO_2_16") (pintype "passive"))
      (node (ref "Q2") (pin "1") (pinfunction "G_1") (pintype "passive"))
      (node (ref "R7") (pin "2") (pinfunction "2_2") (pintype "passive"))
      (node (ref "TP2") (pin "1") (pinfunction "G9_1") (pintype "passive"))
    )
    (net (code "23") (name "Net-(*PWM1-VS_1)") (class "Default")
      (node (ref "*PWM1") (pin "13") (pinfunction "VS_1_13") (pintype "passive"))
      (node (ref "Q3") (pin "3") (pinfunction "E_3") (pintype "passive"))
      (node (ref "Q4") (pin "2") (pinfunction "C_2") (pintype "passive"))
      (node (ref "R9") (pin "1") (pinfunction "1_1") (pintype "passive"))
      (node (ref "T1") (pin "1") (pinfunction "3_1") (pintype "passive"))
      (node (ref "TP11") (pin "1") (pinfunction "G9_1") (pintype "passive"))
    )
    (net (code "24") (name "Net-(*PWM1-VS_2)") (class "Default")
      (node (ref "*PWM1") (pin "17") (pinfunction "VS_2_17") (pintype "passive"))
      (node (ref "C10") (pin "2") (pinfunction "2_2") (pintype "passive"))
      (node (ref "C13") (pin "2") (pinfunction "2_2") (pintype "passive"))
      (node (ref "Q1") (pin "3") (pinfunction "E_3") (pintype "passive"))
      (node (ref "Q2") (pin "2") (pinfunction "C_2") (pintype "passive"))
      (node (ref "R4") (pin "1") (pinfunction "1_1") (pintype "passive"))
      (node (ref "TP7") (pin "1") (pinfunction "G9_1") (pintype "passive"))
    )
    (net (code "25") (name "Net-(C2-A)") (class "Default")
      (node (ref "C2") (pin "2") (pinfunction "A_2") (pintype "passive"))
      (node (ref "CN1") (pin "1") (pinfunction "+_1") (pintype "passive"))
      (node (ref "R27") (pin "2") (pinfunction "2_2") (pintype "passive"))
      (node (ref "R30") (pin "2") (pinfunction "2_2") (pintype "passive"))
      (node (ref "TP8") (pin "1") (pinfunction "G9_1") (pintype "passive"))
      (node (ref "VD1") (pin "1") (pinfunction "1_1") (pintype "passive"))
      (node (ref "VD2") (pin "1") (pinfunction "1_1") (pintype "passive"))
    )
    (net (code "26") (name "Net-(C2-C)") (class "Default")
      (node (ref "C2") (pin "1") (pinfunction "C_1") (pintype "passive"))
      (node (ref "C6") (pin "1") (pinfunction "C_1") (pintype "passive"))
      (node (ref "CN1") (pin "2") (pinfunction "-_2") (pintype "passive"))
      (node (ref "L1") (pin "1") (pinfunction "1_1") (pintype "passive"))
      (node (ref "L1") (pin "2") (pinfunction "2_2") (pintype "passive"))
      (node (ref "L1") (pin "3") (pinfunction "3_3") (pintype "passive"))
      (node (ref "L1") (pin "4") (pinfunction "4_4") (pintype "passive"))
      (node (ref "R29") (pin "3") (pinfunction "CW_3") (pintype "passive"))
      (node (ref "R32") (pin "1") (pinfunction "1_1") (pintype "passive"))
      (node (ref "TP19") (pin "1") (pinfunction "G9_1") (pintype "passive"))
      (node (ref "U4") (pin "3") (pinfunction "A_3") (pintype "passive"))
    )
    (net (code "27") (name "Net-(C3-A)") (class "Default")
      (node (ref "C3") (pin "2") (pinfunction "A_2") (pintype "passive"))
      (node (ref "D12") (pin "1") (pinfunction "C_1") (pintype "passive"))
      (node (ref "D15") (pin "1") (pinfunction "C_1") (pintype "passive"))
      (node (ref "TP27") (pin "1") (pinfunction "G9_1") (pintype "passive"))
      (node (ref "U2") (pin "1") (pinfunction "IN_1") (pintype "power_in"))
    )
    (net (code "28") (name "Net-(C4-A)") (class "Default")
      (node (ref "C4") (pin "2") (pinfunction "A_2") (pintype "passive"))
      (node (ref "D11") (pin "2") (pinfunction "A_2") (pintype "passive"))
      (node (ref "TP28") (pin "1") (pinfunction "G9_1") (pintype "passive"))
      (node (ref "U2") (pin "3") (pinfunction "OUT_3") (pintype "power_in"))
      (node (ref "U3") (pin "1") (pinfunction "IN_1") (pintype "power_in"))
    )
    (net (code "29") (name "Net-(C9-C)") (class "Default")
      (node (ref "C9") (pin "1") (pinfunction "C_1") (pintype "passive"))
      (node (ref "R34") (pin "2") (pinfunction "2_2") (pintype "passive"))
    )
    (net (code "30") (name "Net-(C11-Pad1)") (class "Default")
      (node (ref "C11") (pin "1") (pinfunction "1_1") (pintype "passive"))
      (node (ref "R40") (pin "2") (pinfunction "2_2") (pintype "passive"))
    )
    (net (code "31") (name "Net-(D1-A)") (class "Default")
      (node (ref "D1") (pin "3") (pinfunction "A_3") (pintype "passive"))
      (node (ref "D3") (pin "1") (pinfunction "C_1") (pintype "passive"))
      (node (ref "J5") (pin "1") (pinfunction "0_1") (pintype "passive"))
    )
    (net (code "32") (name "Net-(D2-A)") (class "Default")
      (node (ref "D2") (pin "3") (pinfunction "A_3") (pintype "passive"))
      (node (ref "D4") (pin "1") (pinfunction "C_1") (pintype "passive"))
      (node (ref "J4") (pin "1") (pinfunction "0_1") (pintype "passive"))
    )
    (net (code "33") (name "Net-(D3-A)") (class "Default")
      (node (ref "C1") (pin "2") (pinfunction "2_2") (pintype "passive"))
      (node (ref "D3") (pin "3") (pinfunction "A_3") (pintype "passive"))
      (node (ref "D4") (pin "3") (pinfunction "A_3") (pintype "passive"))
      (node (ref "R1") (pin "1") (pinfunction "1_1") (pintype "passive"))
      (node (ref "R2") (pin "2") (pinfunction "2_2") (pintype "passive"))
      (node (ref "R26") (pin "2") (pinfunction "2_2") (pintype "passive"))
      (node (ref "R3") (pin "2") (pinfunction "2_2") (pintype "passive"))
      (node (ref "TP12") (pin "1") (pinfunction "G9_1") (pintype "passive"))
    )
    (net (code "34") (name "Net-(D5-K)") (class "Default")
      (node (ref "D5") (pin "2") (pinfunction "K_2") (pintype "passive"))
      (node (ref "D6") (pin "1") (pinfunction "A_1") (pintype "passive"))
      (node (ref "R6") (pin "2") (pinfunction "2_2") (pintype "passive"))
      (node (ref "T1") (pin "3") (pinfunction "3_3") (pintype "passive"))
      (node (ref "TP14") (pin "1") (pinfunction "G9_1") (pintype "passive"))
    )
    (net (code "35") (name "Net-(D6-K)") (class "Default")
      (node (ref "C7") (pin "1") (pinfunction "1_1") (pintype "passive"))
      (node (ref "D6") (pin "2") (pinfunction "K_2") (pintype "passive"))
      (node (ref "D8") (pin "2") (pinfunction "K_2") (pintype "passive"))
      (node (ref "R37") (pin "2") (pinfunction "2_2") (pintype "passive"))
      (node (ref "R38") (pin "2") (pinfunction "2_2") (pintype "passive"))
      (node (ref "R8") (pin "1") (pinfunction "CCW_1") (pintype "passive"))
      (node (ref "TP15") (pin "1") (pinfunction "G9_1") (pintype "passive"))
    )
    (net (code "36") (name "Net-(D7-K)") (class "Default")
      (node (ref "D7") (pin "2") (pinfunction "K_2") (pintype "passive"))
      (node (ref "D8") (pin "1") (pinfunction "A_1") (pintype "passive"))
      (node (ref "R6") (pin "1") (pinfunction "1_1") (pintype "passive"))
      (node (ref "T1") (pin "4") (pinfunction "4_4") (pintype "passive"))
      (node (ref "TP16") (pin "1") (pinfunction "G9_1") (pintype "passive"))
    )
    (net (code "37") (name "Net-(D9-A)") (class "Default")
      (node (ref "D9") (pin "1") (pinfunction "A_1") (pintype "passive"))
      (node (ref "J2") (pin "2") (pinfunction "2_2") (pintype "passive"))
      (node (ref "Q5") (pin "2") (pinfunction "D_2") (pintype "passive"))
      (node (ref "R36") (pin "1") (pinfunction "1_1") (pintype "passive"))
      (node (ref "TP35") (pin "1") (pinfunction "G9_1") (pintype "passive"))
    )
    (net (code "38") (name "Net-(D10-A)") (class "Default")
      (node (ref "D10") (pin "1") (pinfunction "A_1") (pintype "passive"))
      (node (ref "R11") (pin "1") (pinfunction "1_1") (pintype "passive"))
      (node (ref "R22") (pin "2") (pinfunction "2_2") (pintype "passive"))
      (node (ref "TP32") (pin "1") (pinfunction "G9_1") (pintype "passive"))
      (node (ref "U1") (pin "1") (pinfunction "1OUT_1") (pintype "output"))
    )
    (net (code "39") (name "Net-(D10-K)") (class "Default")
      (node (ref "D10") (pin "2") (pinfunction "K_2") (pintype "passive"))
      (node (ref "D14") (pin "2") (pinfunction "K_2") (pintype "passive"))
      (node (ref "Q5") (pin "1") (pinfunction "G_1") (pintype "passive"))
      (node (ref "R15") (pin "2") (pinfunction "2_2") (pintype "passive"))
      (node (ref "R25") (pin "2") (pinfunction "2_2") (pintype "passive"))
      (node (ref "TP34") (pin "1") (pinfunction "G9_1") (pintype "passive"))
    )
    (net (code "40") (name "Net-(D14-A)") (class "Default")
      (node (ref "D14") (pin "1") (pinfunction "A_1") (pintype "passive"))
      (node (ref "R20") (pin "1") (pinfunction "1_1") (pintype "passive"))
      (node (ref "R23") (pin "2") (pinfunction "2_2") (pintype "passive"))
      (node (ref "TP37") (pin "1") (pinfunction "G9_1") (pintype "passive"))
      (node (ref "U1") (pin "7") (pinfunction "2OUT_7") (pintype "output"))
    )
    (net (code "41") (name "Net-(D17-A)") (class "Default")
      (node (ref "D17") (pin "1") (pinfunction "A_1") (pintype "passive"))
      (node (ref "R24") (pin "1") (pinfunction "1_1") (pintype "passive"))
    )
    (net (code "42") (name "Net-(D18-A)") (class "Default")
      (node (ref "D18") (pin "1") (pinfunction "A_1") (pintype "passive"))
      (node (ref "R25") (pin "1") (pinfunction "1_1") (pintype "passive"))
    )
    (net (code "43") (name "Net-(D19-A)") (class "Default")
      (node (ref "D19") (pin "1") (pinfunction "A_1") (pintype "passive"))
      (node (ref "R31") (pin "1") (pinfunction "1_1") (pintype "passive"))
    )
    (net (code "44") (name "Net-(D20-A)") (class "Default")
      (node (ref "D20") (pin "2") (pinfunction "A_2") (pintype "passive"))
      (node (ref "R34") (pin "1") (pinfunction "1_1") (pintype "passive"))
      (node (ref "R35") (pin "1") (pinfunction "1_1") (pintype "passive"))
    )
    (net (code "45") (name "Net-(D21-A)") (class "Default")
      (node (ref "D21") (pin "1") (pinfunction "A_1") (pintype "passive"))
      (node (ref "R38") (pin "1") (pinfunction "1_1") (pintype "passive"))
    )
    (net (code "46") (name "Net-(J1-L)") (class "Default")
      (node (ref "J1") (pin "3") (pinfunction "L_3") (pintype "passive"))
      (node (ref "J7") (pin "1") (pinfunction "0_1") (pintype "passive"))
    )
    (net (code "47") (name "Net-(J1-N)") (class "Default")
      (node (ref "J1") (pin "1") (pinfunction "N_1") (pintype "passive"))
      (node (ref "J8") (pin "1") (pinfunction "0_1") (pintype "passive"))
    )
    (net (code "48") (name "Net-(R12-Pad1)") (class "Default")
      (node (ref "R12") (pin "1") (pinfunction "1_1") (pintype "passive"))
      (node (ref "R13") (pin "2") (pinfunction "2_2") (pintype "passive"))
    )
    (net (code "49") (name "Net-(R13-Pad1)") (class "Default")
      (node (ref "R13") (pin "1") (pinfunction "1_1") (pintype "passive"))
      (node (ref "R16") (pin "2") (pinfunction "2_2") (pintype "passive"))
    )
    (net (code "50") (name "Net-(R14-WIPER)") (class "Default")
      (node (ref "R14") (pin "2") (pinfunction "WIPER_2") (pintype "passive"))
      (node (ref "TP36") (pin "1") (pinfunction "G9_1") (pintype "passive"))
      (node (ref "U1") (pin "2") (pinfunction "IN1-_2") (pintype "tri_state"))
    )
    (net (code "51") (name "Net-(R19-CW)") (class "Default")
      (node (ref "J3") (pin "1") (pinfunction "1_1") (pintype "passive"))
      (node (ref "R19") (pin "3") (pinfunction "CW_3") (pintype "passive"))
      (node (ref "TP39") (pin "1") (pinfunction "G9_1") (pintype "passive"))
      (node (ref "U1") (pin "6") (pinfunction "IN2-_6") (pintype "tri_state"))
    )
    (net (code "52") (name "Net-(R29-CCW)") (class "Default")
      (node (ref "R27") (pin "1") (pinfunction "1_1") (pintype "passive"))
      (node (ref "R29") (pin "1") (pinfunction "CCW_1") (pintype "passive"))
    )
    (net (code "53") (name "Net-(R29-WIPER)") (class "Default")
      (node (ref "R29") (pin "2") (pinfunction "WIPER_2") (pintype "passive"))
      (node (ref "U4") (pin "2") (pinfunction "REF_2") (pintype "input"))
    )
    (net (code "54") (name "Net-(T1A-4)") (class "Default")
      (node (ref "R40") (pin "1") (pinfunction "1_1") (pintype "passive"))
      (node (ref "T1") (pin "2") (pinfunction "4_2") (pintype "passive"))
      (node (ref "T2") (pin "1") (pinfunction "1_1") (pintype "passive"))
      (node (ref "TP23") (pin "1") (pinfunction "G9_1") (pintype "passive"))
    )
    (net (code "55") (name "Net-(TP18-G9)") (class "Default")
      (node (ref "C10") (pin "1") (pinfunction "1_1") (pintype "passive"))
      (node (ref "C11") (pin "2") (pinfunction "2_2") (pintype "passive"))
      (node (ref "C13") (pin "1") (pinfunction "1_1") (pintype "passive"))
      (node (ref "T2") (pin "2") (pinfunction "2_2") (pintype "passive"))
      (node (ref "TP18") (pin "1") (pinfunction "G9_1") (pintype "passive"))
    )
    (net (code "56") (name "Net-(TP22-G9)") (class "Default")
      (node (ref "L1") (pin "5") (pinfunction "5_5") (pintype "passive"))
      (node (ref "L1") (pin "6") (pinfunction "6_6") (pintype "passive"))
      (node (ref "L1") (pin "7") (pinfunction "7_7") (pintype "passive"))
      (node (ref "L1") (pin "8") (pinfunction "8_8") (pintype "passive"))
      (node (ref "T2") (pin "10") (pinfunction "10_10") (pintype "passive"))
      (node (ref "T2") (pin "5") (pinfunction "5_5") (pintype "passive"))
      (node (ref "TP22") (pin "1") (pinfunction "G9_1") (pintype "passive"))
    )
    (net (code "57") (name "Net-(TP30-G9)") (class "Default")
      (node (ref "T2") (pin "9") (pinfunction "9_9") (pintype "passive"))
      (node (ref "TP30") (pin "1") (pinfunction "G9_1") (pintype "passive"))
      (node (ref "VD1") (pin "2") (pinfunction "2_2") (pintype "passive"))
    )
    (net (code "58") (name "Net-(TP31-G9)") (class "Default")
      (node (ref "T2") (pin "6") (pinfunction "6_6") (pintype "passive"))
      (node (ref "TP31") (pin "1") (pinfunction "G9_1") (pintype "passive"))
      (node (ref "VD2") (pin "2") (pinfunction "2_2") (pintype "passive"))
    )
    (net (code "59") (name "Net-(TP38-G9)") (class "Default")
      (node (ref "R18") (pin "1") (pinfunction "1_1") (pintype "passive"))
      (node (ref "R20") (pin "2") (pinfunction "2_2") (pintype "passive"))
      (node (ref "R21") (pin "2") (pinfunction "2_2") (pintype "passive"))
      (node (ref "TP38") (pin "1") (pinfunction "G9_1") (pintype "passive"))
      (node (ref "U1") (pin "5") (pinfunction "IN2+_5") (pintype "tri_state"))
    )
    (net (code "60") (name "PE") (class "Default")
      (node (ref "J1") (pin "2") (pinfunction "E_2") (pintype "passive"))
      (node (ref "J6") (pin "1") (pinfunction "0_1") (pintype "passive"))
      (node (ref "J9") (pin "1") (pinfunction "0_1") (pintype "passive"))
    )
    (net (code "61") (name "VCC") (class "Default")
      (node (ref "C12") (pin "1") (pinfunction "1_1") (pintype "passive"))
      (node (ref "C8") (pin "1") (pinfunction "1_1") (pintype "passive"))
      (node (ref "C9") (pin "2") (pinfunction "A_2") (pintype "passive"))
      (node (ref "K1") (pin "1") (pinfunction "1_1") (pintype "passive"))
      (node (ref "Q1") (pin "2") (pinfunction "C_2") (pintype "passive"))
      (node (ref "Q3") (pin "2") (pinfunction "C_2") (pintype "passive"))
      (node (ref "R33") (pin "2") (pinfunction "2_2") (pintype "passive"))
      (node (ref "R35") (pin "2") (pinfunction "2_2") (pintype "passive"))
    )
  )
)
